# Sch_Master_Screen.net
KiCad netlist of a schematic drawn in Altium Designer
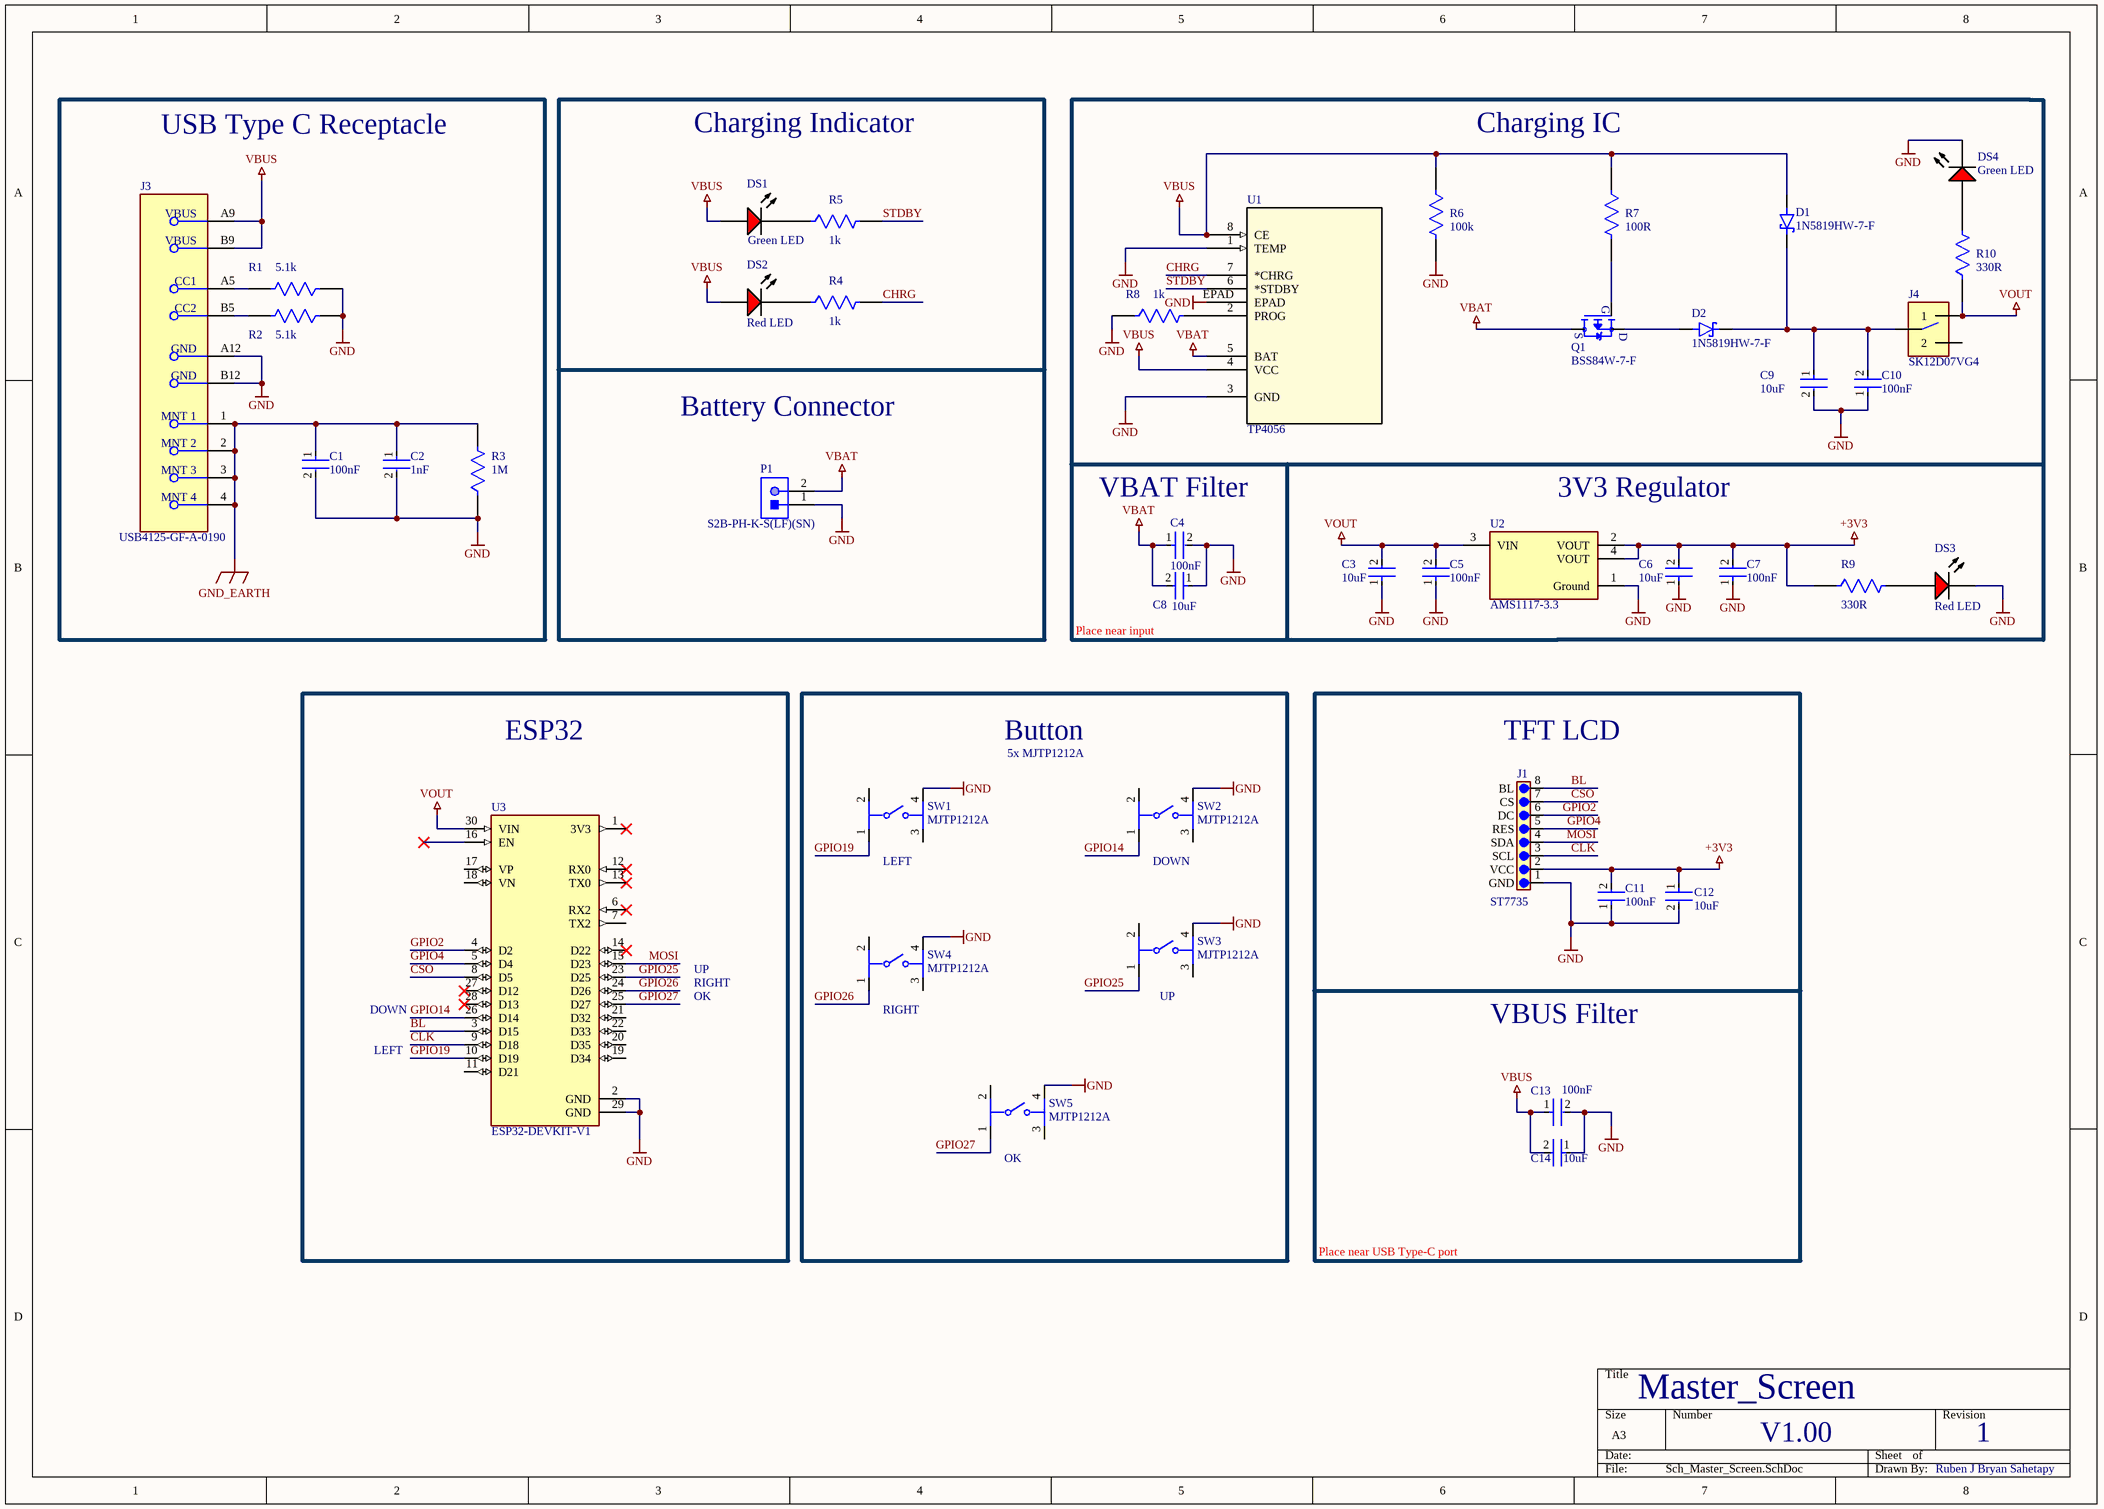
[diagram p0: Sch_Master_Screen.SchDoc]

(export (version "E")
  (design (tool "Eeschema 10.0.6"))
  (components
    (comp (ref "C1")
      (value "100nF")
      (footprint "FP-CC0805-0_85-MFG")
      (description "CAP CER 0.1UF 16V X7R 0805")
      (fields
        (field (name "MANUFACTURER PART NUMBER") "CC0805KRX7R7BB104")
        (field (name "MANUFACTURER") "Yageo")
      )
      (libsource (lib "Altium Content Vault") (part "11868f565c42a9108669ba33697ecf6"))
    )
    (comp (ref "C2")
      (value "1nF")
      (footprint "FP-CC0805-0_85-MFG")
      (description "CAP CER 0.1UF 16V X7R 0805")
      (fields
        (field (name "MANUFACTURER PART NUMBER") "CC0805KRX7R7BB104")
        (field (name "MANUFACTURER") "Yageo")
      )
      (libsource (lib "Altium Content Vault") (part "11868f565c42a9108669ba33697ecf6"))
    )
    (comp (ref "C3")
      (value "10uF")
      (footprint "FP-CC0805-0_85-MFG")
      (description "CAP CER 0.1UF 16V X7R 0805")
      (fields
        (field (name "MANUFACTURER PART NUMBER") "CC0805KRX7R7BB104")
        (field (name "MANUFACTURER") "Yageo")
      )
      (libsource (lib "Altium Content Vault") (part "11868f565c42a9108669ba33697ecf6"))
    )
    (comp (ref "C4")
      (value "100nF")
      (footprint "FP-CC0805-0_85-MFG")
      (description "CAP CER 0.1UF 16V X7R 0805")
      (fields
        (field (name "MANUFACTURER PART NUMBER") "CC0805KRX7R7BB104")
        (field (name "MANUFACTURER") "Yageo")
      )
      (libsource (lib "Altium Content Vault") (part "11868f565c42a9108669ba33697ecf6"))
    )
    (comp (ref "C5")
      (value "100nF")
      (footprint "FP-CC0805-0_85-MFG")
      (description "CAP CER 0.1UF 16V X7R 0805")
      (fields
        (field (name "MANUFACTURER PART NUMBER") "CC0805KRX7R7BB104")
        (field (name "MANUFACTURER") "Yageo")
      )
      (libsource (lib "Altium Content Vault") (part "11868f565c42a9108669ba33697ecf6"))
    )
    (comp (ref "C6")
      (value "10uF")
      (footprint "FP-CC0805-0_85-MFG")
      (description "CAP CER 0.1UF 16V X7R 0805")
      (fields
        (field (name "MANUFACTURER PART NUMBER") "CC0805KRX7R7BB104")
        (field (name "MANUFACTURER") "Yageo")
      )
      (libsource (lib "Altium Content Vault") (part "11868f565c42a9108669ba33697ecf6"))
    )
    (comp (ref "C7")
      (value "100nF")
      (footprint "FP-CC0805-0_85-MFG")
      (description "CAP CER 0.1UF 16V X7R 0805")
      (fields
        (field (name "MANUFACTURER PART NUMBER") "CC0805KRX7R7BB104")
        (field (name "MANUFACTURER") "Yageo")
      )
      (libsource (lib "Altium Content Vault") (part "11868f565c42a9108669ba33697ecf6"))
    )
    (comp (ref "C8")
      (value "10uF")
      (footprint "FP-CC0805-0_85-MFG")
      (description "CAP CER 0.1UF 16V X7R 0805")
      (fields
        (field (name "MANUFACTURER PART NUMBER") "CC0805KRX7R7BB104")
        (field (name "MANUFACTURER") "Yageo")
      )
      (libsource (lib "Altium Content Vault") (part "11868f565c42a9108669ba33697ecf6"))
    )
    (comp (ref "C9")
      (value "10uF")
      (footprint "FP-CC0805-0_85-MFG")
      (description "CAP CER 0.1UF 16V X7R 0805")
      (fields
        (field (name "MANUFACTURER PART NUMBER") "CC0805KRX7R7BB104")
        (field (name "MANUFACTURER") "Yageo")
      )
      (libsource (lib "Altium Content Vault") (part "11868f565c42a9108669ba33697ecf6"))
    )
    (comp (ref "C10")
      (value "100nF")
      (footprint "FP-CC0805-0_85-MFG")
      (description "CAP CER 0.1UF 16V X7R 0805")
      (fields
        (field (name "MANUFACTURER PART NUMBER") "CC0805KRX7R7BB104")
        (field (name "MANUFACTURER") "Yageo")
      )
      (libsource (lib "Altium Content Vault") (part "11868f565c42a9108669ba33697ecf6"))
    )
    (comp (ref "C11")
      (value "100nF")
      (footprint "FP-CC0805-0_85-MFG")
      (description "CAP CER 0.1UF 16V X7R 0805")
      (fields
        (field (name "MANUFACTURER PART NUMBER") "CC0805KRX7R7BB104")
        (field (name "MANUFACTURER") "Yageo")
      )
      (libsource (lib "Altium Content Vault") (part "11868f565c42a9108669ba33697ecf6"))
    )
    (comp (ref "C12")
      (value "10uF")
      (footprint "FP-CC0805-0_85-MFG")
      (description "CAP CER 0.1UF 16V X7R 0805")
      (fields
        (field (name "MANUFACTURER PART NUMBER") "CC0805KRX7R7BB104")
        (field (name "MANUFACTURER") "Yageo")
      )
      (libsource (lib "Altium Content Vault") (part "11868f565c42a9108669ba33697ecf6"))
    )
    (comp (ref "C13")
      (value "100nF")
      (footprint "FP-CC0805-0_85-MFG")
      (description "CAP CER 0.1UF 16V X7R 0805")
      (fields
        (field (name "MANUFACTURER PART NUMBER") "CC0805KRX7R7BB104")
        (field (name "MANUFACTURER") "Yageo")
      )
      (libsource (lib "Altium Content Vault") (part "11868f565c42a9108669ba33697ecf6"))
    )
    (comp (ref "C14")
      (value "10uF")
      (footprint "FP-CC0805-0_85-MFG")
      (description "CAP CER 0.1UF 16V X7R 0805")
      (fields
        (field (name "MANUFACTURER PART NUMBER") "CC0805KRX7R7BB104")
        (field (name "MANUFACTURER") "Yageo")
      )
      (libsource (lib "Altium Content Vault") (part "11868f565c42a9108669ba33697ecf6"))
    )
    (comp (ref "D1")
      (value "1N5819HW-7-F")
      (footprint "SOD3715X145N")
      (description "Schottky Diodes & Rectifiers SOD-123")
      (fields (field (name "MF") "Diodes Inc."))
      (libsource (lib "MarbleLib") (part "1N5819HW-7-F"))
    )
    (comp (ref "D2")
      (value "1N5819HW-7-F")
      (footprint "SOD3715X145N")
      (description "Schottky Diodes & Rectifiers SOD-123")
      (fields (field (name "MF") "Diodes Inc."))
      (libsource (lib "MarbleLib") (part "1N5819HW-7-F"))
    )
    (comp (ref "DS1")
      (value "Green LED")
      (footprint "LUMX-SML-LX1206IC_V")
      (description "LED Red, 65 mW, -40 to 85 degC, 2-Pin SMD, RoHS, Tape and Reel")
      (fields (field (name "MANUFACTURER") "Lumex") (field (name "PART NO") "SML-LX1206IC-TR"))
      (libsource (lib "Altium Content Vault") (part "LED-RED-AK-2"))
    )
    (comp (ref "DS2")
      (value "Red LED")
      (footprint "LUMX-SML-LX1206IC_V")
      (description "LED Red, 65 mW, -40 to 85 degC, 2-Pin SMD, RoHS, Tape and Reel")
      (fields (field (name "MANUFACTURER") "Lumex") (field (name "PART NO") "SML-LX1206IC-TR"))
      (libsource (lib "Altium Content Vault") (part "LED-RED-AK-2"))
    )
    (comp (ref "DS3")
      (value "Red LED")
      (footprint "LUMX-SML-LX1206IC_V")
      (description "LED Red, 65 mW, -40 to 85 degC, 2-Pin SMD, RoHS, Tape and Reel")
      (fields (field (name "MANUFACTURER") "Lumex") (field (name "PART NO") "SML-LX1206IC-TR"))
      (libsource (lib "Altium Content Vault") (part "LED-RED-AK-2"))
    )
    (comp (ref "DS4")
      (value "Green LED")
      (footprint "LUMX-SML-LX1206IC_V")
      (description "LED Red, 65 mW, -40 to 85 degC, 2-Pin SMD, RoHS, Tape and Reel")
      (fields (field (name "MANUFACTURER") "Lumex") (field (name "PART NO") "SML-LX1206IC-TR"))
      (libsource (lib "Altium Content Vault") (part "LED-RED-AK-2"))
    )
    (comp (ref "J1")
      (value "ST7735")
      (footprint "ST7735")
      (description "1.8 inches 128x160 RGB TFT LCD - ST7735 DRIVER")
      (fields (field (name "PART NUMBER") "TFT-ST7735"))
      (libsource (lib "MarbleLib") (part "ST7735"))
    )
    (comp (ref "J3")
      (value "USB4125-GF-A-0190")
      (footprint "FP-USB4125-GF-A-0190-MFG")
      (description "CONN RCPT TYPE C 6P SMD RA")
      (libsource (lib "Altium Content Vault") (part "a055484d46e58b234844902c9fd883a"))
    )
    (comp (ref "J4")
      (value "SK12D07VG4")
      (footprint "SK12D07VG4")
      (description "Slide Switches - Side Knob")
      (fields (field (name "MF") "C&K"))
      (libsource (lib "MarbleLib") (part "SK12D07VG4"))
    )
    (comp (ref "P1")
      (value "S2B-PH-K-S(LF)(SN)")
      (footprint "JST-S2B-PH-K-S_V")
      (fields (field (name "TOLERANCE") "20%"))
      (libsource (lib "Altium Content Vault") (part "CN-1P-M-R2"))
    )
    (comp (ref "Q1")
      (value "BSS84W-7-F")
      (footprint "SOT65P222X110-3N")
      (description "MOSFET P-Channel 50V 130MA SOT323")
      (fields (field (name "MF") "Diodes Inc."))
      (libsource (lib "MarbleLib") (part "BSS84W-7-F"))
    )
    (comp (ref "R1")
      (value "5.1k")
      (footprint "FP-RC1206-MFG")
      (description "RES SMD 0 OHM JUMPER 1/4W 1206")
      (fields
        (field (name "MANUFACTURER PART NUMBER") "RC1206JR-070RL")
        (field (name "MANUFACTURER") "YAGEO")
      )
      (libsource (lib "Altium Content Vault") (part "1029c3af85768c4190bb7ad29bc67b5"))
    )
    (comp (ref "R2")
      (value "5.1k")
      (footprint "FP-RC1206-MFG")
      (description "RES SMD 0 OHM JUMPER 1/4W 1206")
      (fields
        (field (name "MANUFACTURER PART NUMBER") "RC1206JR-070RL")
        (field (name "MANUFACTURER") "YAGEO")
      )
      (libsource (lib "Altium Content Vault") (part "1029c3af85768c4190bb7ad29bc67b5"))
    )
    (comp (ref "R3")
      (value "1M")
      (footprint "FP-RC1206-MFG")
      (description "RES SMD 0 OHM JUMPER 1/4W 1206")
      (fields
        (field (name "MANUFACTURER PART NUMBER") "RC1206JR-070RL")
        (field (name "MANUFACTURER") "YAGEO")
      )
      (libsource (lib "Altium Content Vault") (part "1029c3af85768c4190bb7ad29bc67b5"))
    )
    (comp (ref "R4")
      (value "1k")
      (footprint "FP-RC1206-MFG")
      (description "RES SMD 0 OHM JUMPER 1/4W 1206")
      (fields
        (field (name "MANUFACTURER PART NUMBER") "RC1206JR-070RL")
        (field (name "MANUFACTURER") "YAGEO")
      )
      (libsource (lib "Altium Content Vault") (part "1029c3af85768c4190bb7ad29bc67b5"))
    )
    (comp (ref "R5")
      (value "1k")
      (footprint "FP-RC1206-MFG")
      (description "RES SMD 0 OHM JUMPER 1/4W 1206")
      (fields
        (field (name "MANUFACTURER PART NUMBER") "RC1206JR-070RL")
        (field (name "MANUFACTURER") "YAGEO")
      )
      (libsource (lib "Altium Content Vault") (part "1029c3af85768c4190bb7ad29bc67b5"))
    )
    (comp (ref "R6")
      (value "100k")
      (footprint "FP-RC1206-MFG")
      (description "RES SMD 0 OHM JUMPER 1/4W 1206")
      (fields
        (field (name "MANUFACTURER PART NUMBER") "RC1206JR-070RL")
        (field (name "MANUFACTURER") "YAGEO")
      )
      (libsource (lib "Altium Content Vault") (part "1029c3af85768c4190bb7ad29bc67b5"))
    )
    (comp (ref "R7")
      (value "100R")
      (footprint "FP-RC1206-MFG")
      (description "RES SMD 0 OHM JUMPER 1/4W 1206")
      (fields
        (field (name "MANUFACTURER PART NUMBER") "RC1206JR-070RL")
        (field (name "MANUFACTURER") "YAGEO")
      )
      (libsource (lib "Altium Content Vault") (part "1029c3af85768c4190bb7ad29bc67b5"))
    )
    (comp (ref "R8")
      (value "1k")
      (footprint "FP-RC1206-MFG")
      (description "RES SMD 0 OHM JUMPER 1/4W 1206")
      (fields
        (field (name "MANUFACTURER PART NUMBER") "RC1206JR-070RL")
        (field (name "MANUFACTURER") "YAGEO")
      )
      (libsource (lib "Altium Content Vault") (part "1029c3af85768c4190bb7ad29bc67b5"))
    )
    (comp (ref "R9")
      (value "330R")
      (footprint "FP-RC1206-MFG")
      (description "RES SMD 0 OHM JUMPER 1/4W 1206")
      (fields
        (field (name "MANUFACTURER PART NUMBER") "RC1206JR-070RL")
        (field (name "MANUFACTURER") "YAGEO")
      )
      (libsource (lib "Altium Content Vault") (part "1029c3af85768c4190bb7ad29bc67b5"))
    )
    (comp (ref "R10")
      (value "330R")
      (footprint "FP-RC1206-MFG")
      (description "RES SMD 0 OHM JUMPER 1/4W 1206")
      (fields
        (field (name "MANUFACTURER PART NUMBER") "RC1206JR-070RL")
        (field (name "MANUFACTURER") "YAGEO")
      )
      (libsource (lib "Altium Content Vault") (part "1029c3af85768c4190bb7ad29bc67b5"))
    )
    (comp (ref "SW1")
      (value "MJTP1212A")
      (footprint "FP-MJTP1212A-MFG")
      (description "Switch Tactile Button 12x12mm")
      (libsource (lib "MarbleLib") (part "CMP-47024-000003-1"))
    )
    (comp (ref "SW2")
      (value "MJTP1212A")
      (footprint "FP-MJTP1212A-MFG")
      (description "Switch Tactile Button 12x12mm")
      (libsource (lib "MarbleLib") (part "CMP-47024-000003-1"))
    )
    (comp (ref "SW3")
      (value "MJTP1212A")
      (footprint "FP-MJTP1212A-MFG")
      (description "Switch Tactile Button 12x12mm")
      (libsource (lib "MarbleLib") (part "CMP-47024-000003-1"))
    )
    (comp (ref "SW4")
      (value "MJTP1212A")
      (footprint "FP-MJTP1212A-MFG")
      (description "Switch Tactile Button 12x12mm")
      (libsource (lib "MarbleLib") (part "CMP-47024-000003-1"))
    )
    (comp (ref "SW5")
      (value "MJTP1212A")
      (footprint "FP-MJTP1212A-MFG")
      (description "Switch Tactile Button 12x12mm")
      (libsource (lib "MarbleLib") (part "CMP-47024-000003-1"))
    )
    (comp (ref "U1")
      (value "TP4056")
      (footprint "SOP8-PP_TPW")
      (description "charger for single cell lithium-ion batteries")
      (fields (field (name "COPYRIGHT") "Copyright (C) 2025 Ultra Librarian. All rights reserved."))
      (libsource (lib "MarbleLib") (part "TP4056"))
    )
    (comp (ref "U2")
      (value "AMS1117-3.3")
      (footprint "FP-AMS1117-IPC_C")
      (description "LDO Voltage Regulators 1A, 3.3V")
      (fields
        (field (name "OCTOPART") "https://octopart.com/ams1117-3.3-advanced+monolithic+systems-25899300")
        (field (name "MANUFACTURER") "Advanced Monolithic Systems")
      )
      (libsource (lib "Altium Content Vault") (part "8bdbb5f8e77002000e30dd2845d0354"))
    )
    (comp (ref "U3")
      (value "ESP32-DEVKIT-V1")
      (footprint "MODULE_ESP32_DEVKIT_V1")
      (description "ESP32-DEVKIT-V1 30 Pins")
      (fields (field (name "MF") "Do it"))
      (libsource (lib "MarbleLib") (part "ESP32-DEVKIT-V1"))
    )
  )
  (nets
    (net (code "1") (name "+3V3") (class "Default")
      (node (ref "C11") (pin "2") (pinfunction "2_2") (pintype "passive"))
      (node (ref "C12") (pin "1") (pinfunction "1_1") (pintype "passive"))
      (node (ref "C6") (pin "2") (pinfunction "2_2") (pintype "passive"))
      (node (ref "C7") (pin "2") (pinfunction "2_2") (pintype "passive"))
      (node (ref "J1") (pin "2") (pinfunction "VCC_2") (pintype "passive"))
      (node (ref "R9") (pin "1") (pinfunction "1_1") (pintype "passive"))
      (node (ref "U2") (pin "2") (pinfunction "VOUT_2") (pintype "passive"))
      (node (ref "U2") (pin "4") (pinfunction "VOUT_4") (pintype "passive"))
    )
    (net (code "2") (name "/BL") (class "Default")
      (node (ref "J1") (pin "8") (pinfunction "BL_8") (pintype "passive"))
      (node (ref "U3") (pin "3") (pinfunction "D15_3") (pintype "bidirectional"))
    )
    (net (code "3") (name "/CHRG") (class "Default")
      (node (ref "R4") (pin "2") (pinfunction "2_2") (pintype "passive"))
      (node (ref "U1") (pin "7") (pinfunction "*CHRG_7") (pintype "passive"))
    )
    (net (code "4") (name "/CLK") (class "Default")
      (node (ref "J1") (pin "3") (pinfunction "SCL_3") (pintype "passive"))
      (node (ref "U3") (pin "9") (pinfunction "D18_9") (pintype "bidirectional"))
    )
    (net (code "5") (name "/CSO") (class "Default")
      (node (ref "J1") (pin "7") (pinfunction "CS_7") (pintype "passive"))
      (node (ref "U3") (pin "8") (pinfunction "D5_8") (pintype "bidirectional"))
    )
    (net (code "6") (name "/GPIO2") (class "Default")
      (node (ref "J1") (pin "6") (pinfunction "DC_6") (pintype "passive"))
      (node (ref "U3") (pin "4") (pinfunction "D2_4") (pintype "bidirectional"))
    )
    (net (code "7") (name "/GPIO4") (class "Default")
      (node (ref "J1") (pin "5") (pinfunction "RES_5") (pintype "passive"))
      (node (ref "U3") (pin "5") (pinfunction "D4_5") (pintype "bidirectional"))
    )
    (net (code "8") (name "/GPIO14") (class "Default")
      (node (ref "SW2") (pin "1") (pinfunction "1_1") (pintype "passive"))
      (node (ref "U3") (pin "26") (pinfunction "D14_26") (pintype "bidirectional"))
    )
    (net (code "9") (name "/GPIO19") (class "Default")
      (node (ref "SW1") (pin "1") (pinfunction "1_1") (pintype "passive"))
      (node (ref "U3") (pin "10") (pinfunction "D19_10") (pintype "bidirectional"))
    )
    (net (code "10") (name "/GPIO25") (class "Default")
      (node (ref "SW3") (pin "1") (pinfunction "1_1") (pintype "passive"))
      (node (ref "U3") (pin "23") (pinfunction "D25_23") (pintype "bidirectional"))
    )
    (net (code "11") (name "/GPIO26") (class "Default")
      (node (ref "SW4") (pin "1") (pinfunction "1_1") (pintype "passive"))
      (node (ref "U3") (pin "24") (pinfunction "D26_24") (pintype "bidirectional"))
    )
    (net (code "12") (name "/GPIO27") (class "Default")
      (node (ref "SW5") (pin "1") (pinfunction "1_1") (pintype "passive"))
      (node (ref "U3") (pin "25") (pinfunction "D27_25") (pintype "bidirectional"))
    )
    (net (code "13") (name "/MOSI") (class "Default")
      (node (ref "J1") (pin "4") (pinfunction "SDA_4") (pintype "passive"))
      (node (ref "U3") (pin "15") (pinfunction "D23_15") (pintype "bidirectional"))
    )
    (net (code "14") (name "/STDBY") (class "Default")
      (node (ref "R5") (pin "2") (pinfunction "2_2") (pintype "passive"))
      (node (ref "U1") (pin "6") (pinfunction "*STDBY_6") (pintype "passive"))
    )
    (net (code "15") (name "GND") (class "Default")
      (node (ref "C1") (pin "2") (pinfunction "2_2") (pintype "passive"))
      (node (ref "C10") (pin "1") (pinfunction "1_1") (pintype "passive"))
      (node (ref "C11") (pin "1") (pinfunction "1_1") (pintype "passive"))
      (node (ref "C12") (pin "2") (pinfunction "2_2") (pintype "passive"))
      (node (ref "C13") (pin "2") (pinfunction "2_2") (pintype "passive"))
      (node (ref "C14") (pin "1") (pinfunction "1_1") (pintype "passive"))
      (node (ref "C2") (pin "2") (pinfunction "2_2") (pintype "passive"))
      (node (ref "C3") (pin "1") (pinfunction "1_1") (pintype "passive"))
      (node (ref "C4") (pin "2") (pinfunction "2_2") (pintype "passive"))
      (node (ref "C5") (pin "1") (pinfunction "1_1") (pintype "passive"))
      (node (ref "C6") (pin "1") (pinfunction "1_1") (pintype "passive"))
      (node (ref "C7") (pin "1") (pinfunction "1_1") (pintype "passive"))
      (node (ref "C8") (pin "1") (pinfunction "1_1") (pintype "passive"))
      (node (ref "C9") (pin "2") (pinfunction "2_2") (pintype "passive"))
      (node (ref "DS3") (pin "2") (pinfunction "K_2") (pintype "passive"))
      (node (ref "DS4") (pin "2") (pinfunction "K_2") (pintype "passive"))
      (node (ref "J1") (pin "1") (pinfunction "GND_1") (pintype "passive"))
      (node (ref "J3") (pin "A12") (pinfunction "GND_A12") (pintype "passive"))
      (node (ref "J3") (pin "B12") (pinfunction "GND_B12") (pintype "passive"))
      (node (ref "P1") (pin "1") (pinfunction "1_1") (pintype "passive"))
      (node (ref "R1") (pin "1") (pinfunction "1_1") (pintype "passive"))
      (node (ref "R2") (pin "1") (pinfunction "1_1") (pintype "passive"))
      (node (ref "R3") (pin "1") (pinfunction "1_1") (pintype "passive"))
      (node (ref "R6") (pin "2") (pinfunction "2_2") (pintype "passive"))
      (node (ref "R8") (pin "1") (pinfunction "1_1") (pintype "passive"))
      (node (ref "SW1") (pin "4") (pinfunction "4_4") (pintype "passive"))
      (node (ref "SW2") (pin "4") (pinfunction "4_4") (pintype "passive"))
      (node (ref "SW3") (pin "4") (pinfunction "4_4") (pintype "passive"))
      (node (ref "SW4") (pin "4") (pinfunction "4_4") (pintype "passive"))
      (node (ref "SW5") (pin "4") (pinfunction "4_4") (pintype "passive"))
      (node (ref "U1") (pin "1") (pinfunction "TEMP_1") (pintype "input"))
      (node (ref "U1") (pin "3") (pinfunction "GND_3") (pintype "power_in"))
      (node (ref "U1") (pin "EPAD") (pinfunction "EPAD_EPAD") (pintype "passive"))
      (node (ref "U2") (pin "1") (pinfunction "Ground_1") (pintype "power_in"))
      (node (ref "U3") (pin "2") (pinfunction "GND_2") (pintype "power_in"))
      (node (ref "U3") (pin "29") (pinfunction "GND_29") (pintype "power_in"))
    )
    (net (code "16") (name "GND_EARTH") (class "Default")
      (node (ref "C1") (pin "1") (pinfunction "1_1") (pintype "passive"))
      (node (ref "C2") (pin "1") (pinfunction "1_1") (pintype "passive"))
      (node (ref "J3") (pin "1") (pinfunction "MNT_1_1") (pintype "passive"))
      (node (ref "J3") (pin "2") (pinfunction "MNT_2_2") (pintype "passive"))
      (node (ref "J3") (pin "3") (pinfunction "MNT_3_3") (pintype "passive"))
      (node (ref "J3") (pin "4") (pinfunction "MNT_4_4") (pintype "passive"))
      (node (ref "R3") (pin "2") (pinfunction "2_2") (pintype "passive"))
    )
    (net (code "17") (name "Net-(D1-K)") (class "Default")
      (node (ref "C10") (pin "2") (pinfunction "2_2") (pintype "passive"))
      (node (ref "C9") (pin "1") (pinfunction "1_1") (pintype "passive"))
      (node (ref "D1") (pin "C") (pinfunction "K_C") (pintype "passive"))
      (node (ref "D2") (pin "C") (pinfunction "K_C") (pintype "passive"))
      (node (ref "J4") (pin "COM") (pinfunction "COM_COM") (pintype "passive"))
    )
    (net (code "18") (name "Net-(DS1-K)") (class "Default")
      (node (ref "DS1") (pin "2") (pinfunction "K_2") (pintype "passive"))
      (node (ref "R5") (pin "1") (pinfunction "1_1") (pintype "passive"))
    )
    (net (code "19") (name "Net-(DS2-K)") (class "Default")
      (node (ref "DS2") (pin "2") (pinfunction "K_2") (pintype "passive"))
      (node (ref "R4") (pin "1") (pinfunction "1_1") (pintype "passive"))
    )
    (net (code "20") (name "Net-(DS3-A)") (class "Default")
      (node (ref "DS3") (pin "1") (pinfunction "A_1") (pintype "passive"))
      (node (ref "R9") (pin "2") (pinfunction "2_2") (pintype "passive"))
    )
    (net (code "21") (name "Net-(DS4-A)") (class "Default")
      (node (ref "DS4") (pin "1") (pinfunction "A_1") (pintype "passive"))
      (node (ref "R10") (pin "2") (pinfunction "2_2") (pintype "passive"))
    )
    (net (code "22") (name "Net-(J3-CC1)") (class "Default")
      (node (ref "J3") (pin "A5") (pinfunction "CC1_A5") (pintype "passive"))
      (node (ref "R1") (pin "2") (pinfunction "2_2") (pintype "passive"))
    )
    (net (code "23") (name "Net-(J3-CC2)") (class "Default")
      (node (ref "J3") (pin "B5") (pinfunction "CC2_B5") (pintype "passive"))
      (node (ref "R2") (pin "2") (pinfunction "2_2") (pintype "passive"))
    )
    (net (code "24") (name "Net-(Q1-G)") (class "Default")
      (node (ref "Q1") (pin "1") (pinfunction "G_1") (pintype "passive"))
      (node (ref "R7") (pin "2") (pinfunction "2_2") (pintype "passive"))
    )
    (net (code "25") (name "Net-(Q1-S)") (class "Default")
      (node (ref "D2") (pin "A") (pinfunction "A_A") (pintype "passive"))
      (node (ref "Q1") (pin "2") (pinfunction "S_2") (pintype "passive"))
    )
    (net (code "26") (name "Net-(U1-PROG)") (class "Default")
      (node (ref "R8") (pin "2") (pinfunction "2_2") (pintype "passive"))
      (node (ref "U1") (pin "2") (pinfunction "PROG_2") (pintype "passive"))
    )
    (net (code "27") (name "VBAT") (class "Default")
      (node (ref "C4") (pin "1") (pinfunction "1_1") (pintype "passive"))
      (node (ref "C8") (pin "2") (pinfunction "2_2") (pintype "passive"))
      (node (ref "P1") (pin "2") (pinfunction "2_2") (pintype "passive"))
      (node (ref "Q1") (pin "3") (pinfunction "D_3") (pintype "passive"))
      (node (ref "U1") (pin "5") (pinfunction "BAT_5") (pintype "power_in"))
    )
    (net (code "28") (name "VBUS") (class "Default")
      (node (ref "C13") (pin "1") (pinfunction "1_1") (pintype "passive"))
      (node (ref "C14") (pin "2") (pinfunction "2_2") (pintype "passive"))
      (node (ref "D1") (pin "A") (pinfunction "A_A") (pintype "passive"))
      (node (ref "DS1") (pin "1") (pinfunction "A_1") (pintype "passive"))
      (node (ref "DS2") (pin "1") (pinfunction "A_1") (pintype "passive"))
      (node (ref "J3") (pin "A9") (pinfunction "VBUS_A9") (pintype "passive"))
      (node (ref "J3") (pin "B9") (pinfunction "VBUS_B9") (pintype "passive"))
      (node (ref "R6") (pin "1") (pinfunction "1_1") (pintype "passive"))
      (node (ref "R7") (pin "1") (pinfunction "1_1") (pintype "passive"))
      (node (ref "U1") (pin "4") (pinfunction "VCC_4") (pintype "power_in"))
      (node (ref "U1") (pin "8") (pinfunction "CE_8") (pintype "input"))
    )
    (net (code "29") (name "VOUT") (class "Default")
      (node (ref "C3") (pin "2") (pinfunction "2_2") (pintype "passive"))
      (node (ref "C5") (pin "2") (pinfunction "2_2") (pintype "passive"))
      (node (ref "J4") (pin "1") (pinfunction "1_1") (pintype "passive"))
      (node (ref "R10") (pin "1") (pinfunction "1_1") (pintype "passive"))
      (node (ref "U2") (pin "3") (pinfunction "VIN_3") (pintype "power_in"))
      (node (ref "U3") (pin "30") (pinfunction "VIN_30") (pintype "input"))
    )
    (net (code "30") (name "unconnected-(J4-Pad2)") (class "Default")
      (node (ref "J4") (pin "2") (pinfunction "2_2") (pintype "passive"))
    )
    (net (code "31") (name "unconnected-(SW1-Pad2)") (class "Default")
      (node (ref "SW1") (pin "2") (pinfunction "2_2") (pintype "passive"))
    )
    (net (code "32") (name "unconnected-(SW1-Pad3)") (class "Default")
      (node (ref "SW1") (pin "3") (pinfunction "3_3") (pintype "passive"))
    )
    (net (code "33") (name "unconnected-(SW2-Pad2)") (class "Default")
      (node (ref "SW2") (pin "2") (pinfunction "2_2") (pintype "passive"))
    )
    (net (code "34") (name "unconnected-(SW2-Pad3)") (class "Default")
      (node (ref "SW2") (pin "3") (pinfunction "3_3") (pintype "passive"))
    )
    (net (code "35") (name "unconnected-(SW3-Pad2)") (class "Default")
      (node (ref "SW3") (pin "2") (pinfunction "2_2") (pintype "passive"))
    )
    (net (code "36") (name "unconnected-(SW3-Pad3)") (class "Default")
      (node (ref "SW3") (pin "3") (pinfunction "3_3") (pintype "passive"))
    )
    (net (code "37") (name "unconnected-(SW4-Pad2)") (class "Default")
      (node (ref "SW4") (pin "2") (pinfunction "2_2") (pintype "passive"))
    )
    (net (code "38") (name "unconnected-(SW4-Pad3)") (class "Default")
      (node (ref "SW4") (pin "3") (pinfunction "3_3") (pintype "passive"))
    )
    (net (code "39") (name "unconnected-(SW5-Pad2)") (class "Default")
      (node (ref "SW5") (pin "2") (pinfunction "2_2") (pintype "passive"))
    )
    (net (code "40") (name "unconnected-(SW5-Pad3)") (class "Default")
      (node (ref "SW5") (pin "3") (pinfunction "3_3") (pintype "passive"))
    )
    (net (code "41") (name "unconnected-(U3-3V3-Pad1)") (class "Default")
      (node (ref "U3") (pin "1") (pinfunction "3V3_1") (pintype "output+no_connect"))
    )
    (net (code "42") (name "unconnected-(U3-D12-Pad27)") (class "Default")
      (node (ref "U3") (pin "27") (pinfunction "D12_27") (pintype "bidirectional+no_connect"))
    )
    (net (code "43") (name "unconnected-(U3-D13-Pad28)") (class "Default")
      (node (ref "U3") (pin "28") (pinfunction "D13_28") (pintype "bidirectional+no_connect"))
    )
    (net (code "44") (name "unconnected-(U3-D21-Pad11)") (class "Default")
      (node (ref "U3") (pin "11") (pinfunction "D21_11") (pintype "bidirectional"))
    )
    (net (code "45") (name "unconnected-(U3-D22-Pad14)") (class "Default")
      (node (ref "U3") (pin "14") (pinfunction "D22_14") (pintype "bidirectional+no_connect"))
    )
    (net (code "46") (name "unconnected-(U3-D32-Pad21)") (class "Default")
      (node (ref "U3") (pin "21") (pinfunction "D32_21") (pintype "bidirectional"))
    )
    (net (code "47") (name "unconnected-(U3-D33-Pad22)") (class "Default")
      (node (ref "U3") (pin "22") (pinfunction "D33_22") (pintype "bidirectional"))
    )
    (net (code "48") (name "unconnected-(U3-D34-Pad19)") (class "Default")
      (node (ref "U3") (pin "19") (pinfunction "D34_19") (pintype "bidirectional"))
    )
    (net (code "49") (name "unconnected-(U3-D35-Pad20)") (class "Default")
      (node (ref "U3") (pin "20") (pinfunction "D35_20") (pintype "bidirectional"))
    )
    (net (code "50") (name "unconnected-(U3-EN-Pad16)") (class "Default")
      (node (ref "U3") (pin "16") (pinfunction "EN_16") (pintype "input+no_connect"))
    )
    (net (code "51") (name "unconnected-(U3-RX0-Pad12)") (class "Default")
      (node (ref "U3") (pin "12") (pinfunction "RX0_12") (pintype "input+no_connect"))
    )
    (net (code "52") (name "unconnected-(U3-RX2-Pad6)") (class "Default")
      (node (ref "U3") (pin "6") (pinfunction "RX2_6") (pintype "input+no_connect"))
    )
    (net (code "53") (name "unconnected-(U3-TX0-Pad13)") (class "Default")
      (node (ref "U3") (pin "13") (pinfunction "TX0_13") (pintype "output+no_connect"))
    )
    (net (code "54") (name "unconnected-(U3-TX2-Pad7)") (class "Default")
      (node (ref "U3") (pin "7") (pinfunction "TX2_7") (pintype "output"))
    )
    (net (code "55") (name "unconnected-(U3-VN-Pad18)") (class "Default")
      (node (ref "U3") (pin "18") (pinfunction "VN_18") (pintype "bidirectional"))
    )
    (net (code "56") (name "unconnected-(U3-VP-Pad17)") (class "Default")
      (node (ref "U3") (pin "17") (pinfunction "VP_17") (pintype "bidirectional"))
    )
  )
)
